# SNES_Basic.net
KiCad netlist of a schematic drawn in EAGLE
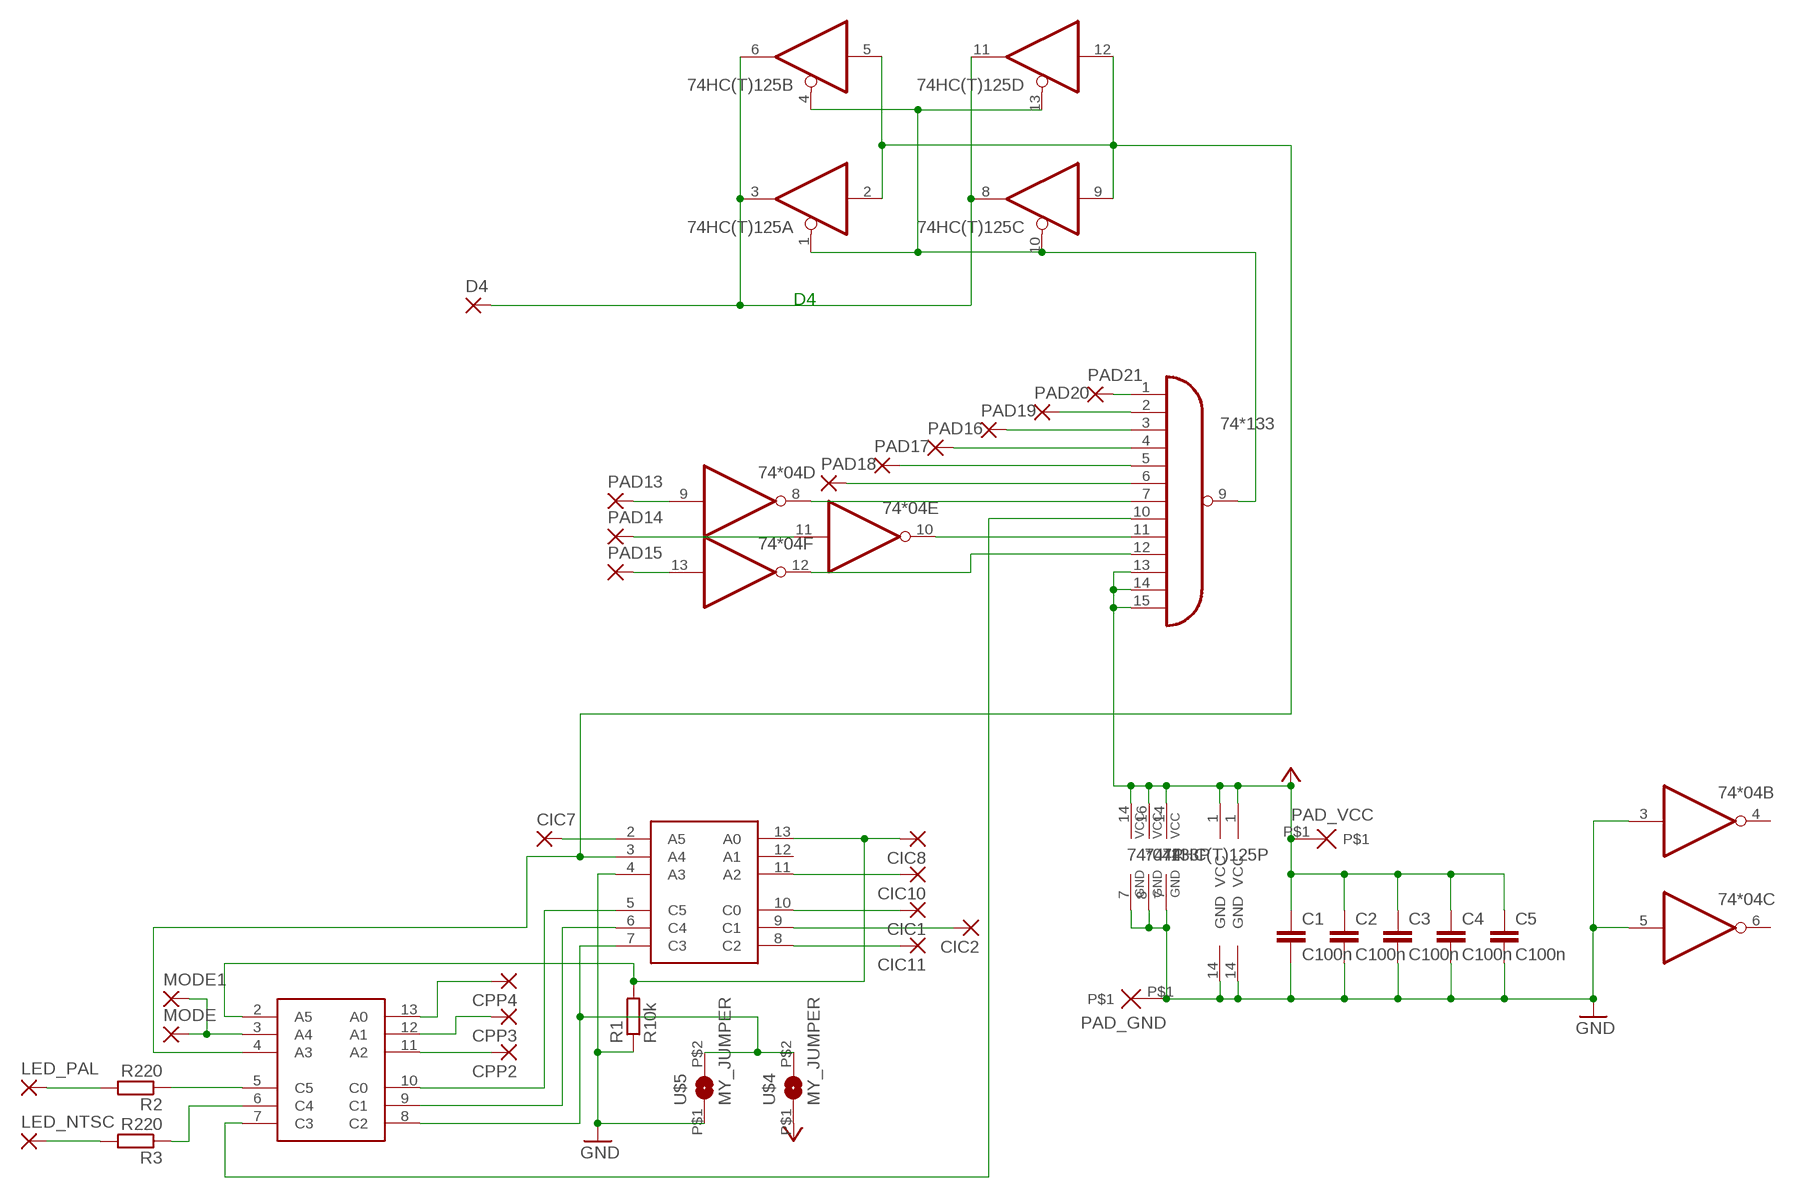
[diagram p0: schematic, sheet 1]

(export (version "E")
  (design (tool "Eeschema 10.0.6"))
  (components
    (comp (ref "74*04")
      (value "74S04D")
      (footprint "eagle-import:SO14")
      (libsource (lib "eagle-import") (part "7404DS"))
    )
    (comp (ref "74*133")
      (value "74S133D")
      (footprint "eagle-import:SO16")
      (libsource (lib "eagle-import") (part "74133DS"))
    )
    (comp (ref "74HC(T)125")
      (value "74HCT125D")
      (footprint "eagle-import:SO14")
      (libsource (lib "eagle-import") (part "74125DHCT"))
    )
    (comp (ref "C1")
      (value "C100n")
      (footprint "eagle-import:Z0805")
      (libsource (lib "eagle-import") (part "C0805"))
    )
    (comp (ref "C2")
      (value "C100n")
      (footprint "eagle-import:Z0805")
      (libsource (lib "eagle-import") (part "C0805"))
    )
    (comp (ref "C3")
      (value "C100n")
      (footprint "eagle-import:Z0805")
      (libsource (lib "eagle-import") (part "C0805"))
    )
    (comp (ref "C4")
      (value "C100n")
      (footprint "eagle-import:Z0805")
      (libsource (lib "eagle-import") (part "C0805"))
    )
    (comp (ref "C5")
      (value "C100n")
      (footprint "eagle-import:Z0805")
      (libsource (lib "eagle-import") (part "C0805"))
    )
    (comp (ref "CIC1")
      (value "SMD2")
      (footprint "eagle-import:SMD1,27-2,54")
      (libsource (lib "eagle-import") (part "SMD2"))
    )
    (comp (ref "CIC2")
      (value "SMD2")
      (footprint "eagle-import:SMD1,27-2,54")
      (libsource (lib "eagle-import") (part "SMD2"))
    )
    (comp (ref "CIC7")
      (value "SMD2")
      (footprint "eagle-import:SMD1,27-2,54")
      (libsource (lib "eagle-import") (part "SMD2"))
    )
    (comp (ref "CIC8")
      (value "SMD2")
      (footprint "eagle-import:SMD1,27-2,54")
      (libsource (lib "eagle-import") (part "SMD2"))
    )
    (comp (ref "CIC10")
      (value "SMD2")
      (footprint "eagle-import:SMD1,27-2,54")
      (libsource (lib "eagle-import") (part "SMD2"))
    )
    (comp (ref "CIC11")
      (value "SMD2")
      (footprint "eagle-import:SMD1,27-2,54")
      (libsource (lib "eagle-import") (part "SMD2"))
    )
    (comp (ref "CPP2")
      (value "SMD2")
      (footprint "eagle-import:SMD1,27-2,54")
      (libsource (lib "eagle-import") (part "SMD2"))
    )
    (comp (ref "CPP3")
      (value "SMD2")
      (footprint "eagle-import:SMD1,27-2,54")
      (libsource (lib "eagle-import") (part "SMD2"))
    )
    (comp (ref "CPP4")
      (value "SMD2")
      (footprint "eagle-import:SMD1,27-2,54")
      (libsource (lib "eagle-import") (part "SMD2"))
    )
    (comp (ref "D4")
      (value "SMD2")
      (footprint "eagle-import:SMD1,27-2,54")
      (libsource (lib "eagle-import") (part "SMD2"))
    )
    (comp (ref "LED_NTSC")
      (value "SMD2")
      (footprint "eagle-import:SMD1,27-2,54")
      (libsource (lib "eagle-import") (part "SMD2"))
    )
    (comp (ref "LED_PAL")
      (value "SMD2")
      (footprint "eagle-import:SMD1,27-2,54")
      (libsource (lib "eagle-import") (part "SMD2"))
    )
    (comp (ref "MODE")
      (value "SMD2")
      (footprint "eagle-import:SMD1,27-2,54")
      (libsource (lib "eagle-import") (part "SMD2"))
    )
    (comp (ref "MODE1")
      (value "SMD2")
      (footprint "eagle-import:SMD1,27-2,54")
      (libsource (lib "eagle-import") (part "SMD2"))
    )
    (comp (ref "PAD13")
      (value "SMD2")
      (footprint "eagle-import:SMD1,27-2,54")
      (libsource (lib "eagle-import") (part "SMD2"))
    )
    (comp (ref "PAD14")
      (value "SMD2")
      (footprint "eagle-import:SMD1,27-2,54")
      (libsource (lib "eagle-import") (part "SMD2"))
    )
    (comp (ref "PAD15")
      (value "SMD2")
      (footprint "eagle-import:SMD1,27-2,54")
      (libsource (lib "eagle-import") (part "SMD2"))
    )
    (comp (ref "PAD16")
      (value "SMD2")
      (footprint "eagle-import:SMD1,27-2,54")
      (libsource (lib "eagle-import") (part "SMD2"))
    )
    (comp (ref "PAD17")
      (value "SMD2")
      (footprint "eagle-import:SMD1,27-2,54")
      (libsource (lib "eagle-import") (part "SMD2"))
    )
    (comp (ref "PAD18")
      (value "SMD2")
      (footprint "eagle-import:SMD1,27-2,54")
      (libsource (lib "eagle-import") (part "SMD2"))
    )
    (comp (ref "PAD19")
      (value "SMD2")
      (footprint "eagle-import:SMD1,27-2,54")
      (libsource (lib "eagle-import") (part "SMD2"))
    )
    (comp (ref "PAD20")
      (value "SMD2")
      (footprint "eagle-import:SMD1,27-2,54")
      (libsource (lib "eagle-import") (part "SMD2"))
    )
    (comp (ref "PAD21")
      (value "SMD2")
      (footprint "eagle-import:SMD1,27-2,54")
      (libsource (lib "eagle-import") (part "SMD2"))
    )
    (comp (ref "PAD_GND")
      (value "PAD")
      (footprint "eagle-import:PADS")
      (libsource (lib "eagle-import") (part "PAD"))
    )
    (comp (ref "PAD_VCC")
      (value "PAD")
      (footprint "eagle-import:PADS")
      (libsource (lib "eagle-import") (part "PAD"))
    )
    (comp (ref "R1")
      (value "R10k")
      (footprint "eagle-import:Z0805")
      (libsource (lib "eagle-import") (part "R0805"))
    )
    (comp (ref "R2")
      (value "R220")
      (footprint "eagle-import:Z0805")
      (libsource (lib "eagle-import") (part "R0805"))
    )
    (comp (ref "R3")
      (value "R220")
      (footprint "eagle-import:Z0805")
      (libsource (lib "eagle-import") (part "R0805"))
    )
    (comp (ref "U$2")
      (value "PIC16F630_SIMPLE")
      (footprint "eagle-import:PIC16F630")
      (libsource (lib "eagle-import") (part "PIC16F630_SIMPLE"))
    )
    (comp (ref "U$3")
      (value "PIC16F630_SIMPLE")
      (footprint "eagle-import:PIC16F630")
      (libsource (lib "eagle-import") (part "PIC16F630_SIMPLE"))
    )
    (comp (ref "U$4")
      (value "MY_JUMPER")
      (footprint "eagle-import:MYJUMP")
      (libsource (lib "eagle-import") (part "MY_JUMPER"))
    )
    (comp (ref "U$5")
      (value "MY_JUMPER")
      (footprint "eagle-import:MYJUMP")
      (libsource (lib "eagle-import") (part "MY_JUMPER"))
    )
  )
  (nets
    (net (code "1") (name "+5V") (class "Default")
      (node (ref "74*04") (pin "14") (pinfunction "VCC_14") (pintype "power_in"))
      (node (ref "74*133") (pin "13") (pinfunction "I10_13") (pintype "input"))
      (node (ref "74*133") (pin "14") (pinfunction "I11_14") (pintype "input"))
      (node (ref "74*133") (pin "15") (pinfunction "I12_15") (pintype "input"))
      (node (ref "74*133") (pin "16") (pinfunction "VCC_16") (pintype "power_in"))
      (node (ref "74HC(T)125") (pin "14") (pinfunction "VCC_14") (pintype "power_in"))
      (node (ref "C1") (pin "1") (pinfunction "1_1") (pintype "passive"))
      (node (ref "C2") (pin "1") (pinfunction "1_1") (pintype "passive"))
      (node (ref "C3") (pin "1") (pinfunction "1_1") (pintype "passive"))
      (node (ref "C4") (pin "1") (pinfunction "1_1") (pintype "passive"))
      (node (ref "C5") (pin "1") (pinfunction "1_1") (pintype "passive"))
      (node (ref "PAD_VCC") (pin "P$1") (pinfunction "P$1_P$1") (pintype "bidirectional"))
      (node (ref "U$2") (pin "1") (pinfunction "VCC_1") (pintype "bidirectional"))
      (node (ref "U$3") (pin "1") (pinfunction "VCC_1") (pintype "bidirectional"))
      (node (ref "U$4") (pin "P$1") (pinfunction "1_P$1") (pintype "passive"))
    )
    (net (code "2") (name "GND") (class "Default")
      (node (ref "74*04") (pin "3") (pinfunction "I_3") (pintype "input"))
      (node (ref "74*04") (pin "5") (pinfunction "I_5") (pintype "input"))
      (node (ref "74*04") (pin "7") (pinfunction "GND_7") (pintype "power_in"))
      (node (ref "74*133") (pin "8") (pinfunction "GND_8") (pintype "power_in"))
      (node (ref "74HC(T)125") (pin "7") (pinfunction "GND_7") (pintype "power_in"))
      (node (ref "C1") (pin "2") (pinfunction "2_2") (pintype "passive"))
      (node (ref "C2") (pin "2") (pinfunction "2_2") (pintype "passive"))
      (node (ref "C3") (pin "2") (pinfunction "2_2") (pintype "passive"))
      (node (ref "C4") (pin "2") (pinfunction "2_2") (pintype "passive"))
      (node (ref "C5") (pin "2") (pinfunction "2_2") (pintype "passive"))
      (node (ref "PAD_GND") (pin "P$1") (pinfunction "P$1_P$1") (pintype "bidirectional"))
      (node (ref "R1") (pin "1") (pinfunction "1_1") (pintype "passive"))
      (node (ref "U$2") (pin "14") (pinfunction "GND_14") (pintype "bidirectional"))
      (node (ref "U$2") (pin "4") (pinfunction "A3_4") (pintype "bidirectional"))
      (node (ref "U$3") (pin "14") (pinfunction "GND_14") (pintype "bidirectional"))
      (node (ref "U$5") (pin "P$1") (pinfunction "1_P$1") (pintype "passive"))
    )
    (net (code "3") (name "Net-(74*04D-I)") (class "Default")
      (node (ref "74*04") (pin "9") (pinfunction "I_9") (pintype "input"))
      (node (ref "PAD13") (pin "1") (pinfunction "P_1") (pintype "passive"))
    )
    (net (code "4") (name "Net-(74*04D-O)") (class "Default")
      (node (ref "74*04") (pin "8") (pinfunction "O_8") (pintype "output"))
      (node (ref "74*133") (pin "7") (pinfunction "I6_7") (pintype "input"))
    )
    (net (code "5") (name "Net-(74*04E-I)") (class "Default")
      (node (ref "74*04") (pin "11") (pinfunction "I_11") (pintype "input"))
      (node (ref "PAD14") (pin "1") (pinfunction "P_1") (pintype "passive"))
    )
    (net (code "6") (name "Net-(74*04E-O)") (class "Default")
      (node (ref "74*04") (pin "10") (pinfunction "O_10") (pintype "output"))
      (node (ref "74*133") (pin "11") (pinfunction "I8_11") (pintype "input"))
    )
    (net (code "7") (name "Net-(74*04F-I)") (class "Default")
      (node (ref "74*04") (pin "13") (pinfunction "I_13") (pintype "input"))
      (node (ref "PAD15") (pin "1") (pinfunction "P_1") (pintype "passive"))
    )
    (net (code "8") (name "Net-(74*04F-O)") (class "Default")
      (node (ref "74*04") (pin "12") (pinfunction "O_12") (pintype "output"))
      (node (ref "74*133") (pin "12") (pinfunction "I9_12") (pintype "input"))
    )
    (net (code "9") (name "Net-(74*133A-I0)") (class "Default")
      (node (ref "74*133") (pin "1") (pinfunction "I0_1") (pintype "input"))
      (node (ref "PAD21") (pin "1") (pinfunction "P_1") (pintype "passive"))
    )
    (net (code "10") (name "Net-(74*133A-I1)") (class "Default")
      (node (ref "74*133") (pin "2") (pinfunction "I1_2") (pintype "input"))
      (node (ref "PAD20") (pin "1") (pinfunction "P_1") (pintype "passive"))
    )
    (net (code "11") (name "Net-(74*133A-I2)") (class "Default")
      (node (ref "74*133") (pin "3") (pinfunction "I2_3") (pintype "input"))
      (node (ref "PAD19") (pin "1") (pinfunction "P_1") (pintype "passive"))
    )
    (net (code "12") (name "Net-(74*133A-I3)") (class "Default")
      (node (ref "74*133") (pin "4") (pinfunction "I3_4") (pintype "input"))
      (node (ref "PAD16") (pin "1") (pinfunction "P_1") (pintype "passive"))
    )
    (net (code "13") (name "Net-(74*133A-I4)") (class "Default")
      (node (ref "74*133") (pin "5") (pinfunction "I4_5") (pintype "input"))
      (node (ref "PAD17") (pin "1") (pinfunction "P_1") (pintype "passive"))
    )
    (net (code "14") (name "Net-(74*133A-I5)") (class "Default")
      (node (ref "74*133") (pin "6") (pinfunction "I5_6") (pintype "input"))
      (node (ref "PAD18") (pin "1") (pinfunction "P_1") (pintype "passive"))
    )
    (net (code "15") (name "Net-(74*133A-I7)") (class "Default")
      (node (ref "74*133") (pin "10") (pinfunction "I7_10") (pintype "input"))
      (node (ref "U$3") (pin "7") (pinfunction "C3_7") (pintype "bidirectional"))
    )
    (net (code "16") (name "Net-(74*133A-O)") (class "Default")
      (node (ref "74*133") (pin "9") (pinfunction "O_9") (pintype "output"))
      (node (ref "74HC(T)125") (pin "1") (pinfunction "OE_1") (pintype "input"))
      (node (ref "74HC(T)125") (pin "10") (pinfunction "OE_10") (pintype "input"))
      (node (ref "74HC(T)125") (pin "13") (pinfunction "OE_13") (pintype "input"))
      (node (ref "74HC(T)125") (pin "4") (pinfunction "OE_4") (pintype "input"))
    )
    (net (code "17") (name "Net-(74HC(T)125A-I)") (class "Default")
      (node (ref "74HC(T)125") (pin "12") (pinfunction "I_12") (pintype "input"))
      (node (ref "74HC(T)125") (pin "2") (pinfunction "I_2") (pintype "input"))
      (node (ref "74HC(T)125") (pin "5") (pinfunction "I_5") (pintype "input"))
      (node (ref "74HC(T)125") (pin "9") (pinfunction "I_9") (pintype "input"))
      (node (ref "U$2") (pin "3") (pinfunction "A4_3") (pintype "bidirectional"))
      (node (ref "U$3") (pin "4") (pinfunction "A3_4") (pintype "bidirectional"))
    )
    (net (code "18") (name "Net-(74HC(T)125A-O)") (class "Default")
      (node (ref "74HC(T)125") (pin "11") (pinfunction "O_11") (pintype "tri_state"))
      (node (ref "74HC(T)125") (pin "3") (pinfunction "O_3") (pintype "tri_state"))
      (node (ref "74HC(T)125") (pin "6") (pinfunction "O_6") (pintype "tri_state"))
      (node (ref "74HC(T)125") (pin "8") (pinfunction "O_8") (pintype "tri_state"))
      (node (ref "D4") (pin "1") (pinfunction "P_1") (pintype "passive"))
    )
    (net (code "19") (name "Net-(CIC1-P)") (class "Default")
      (node (ref "CIC1") (pin "1") (pinfunction "P_1") (pintype "passive"))
      (node (ref "U$2") (pin "10") (pinfunction "C0_10") (pintype "bidirectional"))
    )
    (net (code "20") (name "Net-(CIC2-P)") (class "Default")
      (node (ref "CIC2") (pin "1") (pinfunction "P_1") (pintype "passive"))
      (node (ref "U$2") (pin "9") (pinfunction "C1_9") (pintype "bidirectional"))
    )
    (net (code "21") (name "Net-(CIC7-P)") (class "Default")
      (node (ref "CIC7") (pin "1") (pinfunction "P_1") (pintype "passive"))
      (node (ref "U$2") (pin "2") (pinfunction "A5_2") (pintype "bidirectional"))
    )
    (net (code "22") (name "Net-(CIC8-P)") (class "Default")
      (node (ref "CIC8") (pin "1") (pinfunction "P_1") (pintype "passive"))
      (node (ref "R1") (pin "2") (pinfunction "2_2") (pintype "passive"))
      (node (ref "U$2") (pin "13") (pinfunction "A0_13") (pintype "bidirectional"))
      (node (ref "U$3") (pin "2") (pinfunction "A5_2") (pintype "bidirectional"))
    )
    (net (code "23") (name "Net-(CIC10-P)") (class "Default")
      (node (ref "CIC10") (pin "1") (pinfunction "P_1") (pintype "passive"))
      (node (ref "U$2") (pin "11") (pinfunction "A2_11") (pintype "bidirectional"))
    )
    (net (code "24") (name "Net-(CIC11-P)") (class "Default")
      (node (ref "CIC11") (pin "1") (pinfunction "P_1") (pintype "passive"))
      (node (ref "U$2") (pin "8") (pinfunction "C2_8") (pintype "bidirectional"))
    )
    (net (code "25") (name "Net-(CPP2-P)") (class "Default")
      (node (ref "CPP2") (pin "1") (pinfunction "P_1") (pintype "passive"))
      (node (ref "U$3") (pin "11") (pinfunction "A2_11") (pintype "bidirectional"))
    )
    (net (code "26") (name "Net-(CPP3-P)") (class "Default")
      (node (ref "CPP3") (pin "1") (pinfunction "P_1") (pintype "passive"))
      (node (ref "U$3") (pin "12") (pinfunction "A1_12") (pintype "bidirectional"))
    )
    (net (code "27") (name "Net-(CPP4-P)") (class "Default")
      (node (ref "CPP4") (pin "1") (pinfunction "P_1") (pintype "passive"))
      (node (ref "U$3") (pin "13") (pinfunction "A0_13") (pintype "bidirectional"))
    )
    (net (code "28") (name "Net-(LED_NTSC-P)") (class "Default")
      (node (ref "LED_NTSC") (pin "1") (pinfunction "P_1") (pintype "passive"))
      (node (ref "R3") (pin "2") (pinfunction "2_2") (pintype "passive"))
    )
    (net (code "29") (name "Net-(LED_PAL-P)") (class "Default")
      (node (ref "LED_PAL") (pin "1") (pinfunction "P_1") (pintype "passive"))
      (node (ref "R2") (pin "2") (pinfunction "2_2") (pintype "passive"))
    )
    (net (code "30") (name "Net-(MODE-P)") (class "Default")
      (node (ref "MODE") (pin "1") (pinfunction "P_1") (pintype "passive"))
      (node (ref "MODE1") (pin "1") (pinfunction "P_1") (pintype "passive"))
      (node (ref "U$3") (pin "3") (pinfunction "A4_3") (pintype "bidirectional"))
    )
    (net (code "31") (name "Net-(U$2A-C3)") (class "Default")
      (node (ref "U$2") (pin "7") (pinfunction "C3_7") (pintype "bidirectional"))
      (node (ref "U$3") (pin "8") (pinfunction "C2_8") (pintype "bidirectional"))
      (node (ref "U$4") (pin "P$2") (pinfunction "2_P$2") (pintype "passive"))
      (node (ref "U$5") (pin "P$2") (pinfunction "2_P$2") (pintype "passive"))
    )
    (net (code "32") (name "Net-(U$2A-C4)") (class "Default")
      (node (ref "U$2") (pin "6") (pinfunction "C4_6") (pintype "bidirectional"))
      (node (ref "U$3") (pin "9") (pinfunction "C1_9") (pintype "bidirectional"))
    )
    (net (code "33") (name "Net-(U$2A-C5)") (class "Default")
      (node (ref "U$2") (pin "5") (pinfunction "C5_5") (pintype "bidirectional"))
      (node (ref "U$3") (pin "10") (pinfunction "C0_10") (pintype "bidirectional"))
    )
    (net (code "34") (name "Net-(U$3A-C4)") (class "Default")
      (node (ref "R3") (pin "1") (pinfunction "1_1") (pintype "passive"))
      (node (ref "U$3") (pin "6") (pinfunction "C4_6") (pintype "bidirectional"))
    )
    (net (code "35") (name "Net-(U$3A-C5)") (class "Default")
      (node (ref "R2") (pin "1") (pinfunction "1_1") (pintype "passive"))
      (node (ref "U$3") (pin "5") (pinfunction "C5_5") (pintype "bidirectional"))
    )
    (net (code "36") (name "unconnected-(74*04B-O-Pad4)") (class "Default")
      (node (ref "74*04") (pin "4") (pinfunction "O_4") (pintype "output"))
    )
    (net (code "37") (name "unconnected-(74*04C-O-Pad6)") (class "Default")
      (node (ref "74*04") (pin "6") (pinfunction "O_6") (pintype "output"))
    )
    (net (code "38") (name "unconnected-(U$2A-A1-Pad12)") (class "Default")
      (node (ref "U$2") (pin "12") (pinfunction "A1_12") (pintype "bidirectional"))
    )
  )
)
